# suns_wifi_egse_top_connectors.net
KiCad netlist of a schematic drawn in Altium Designer
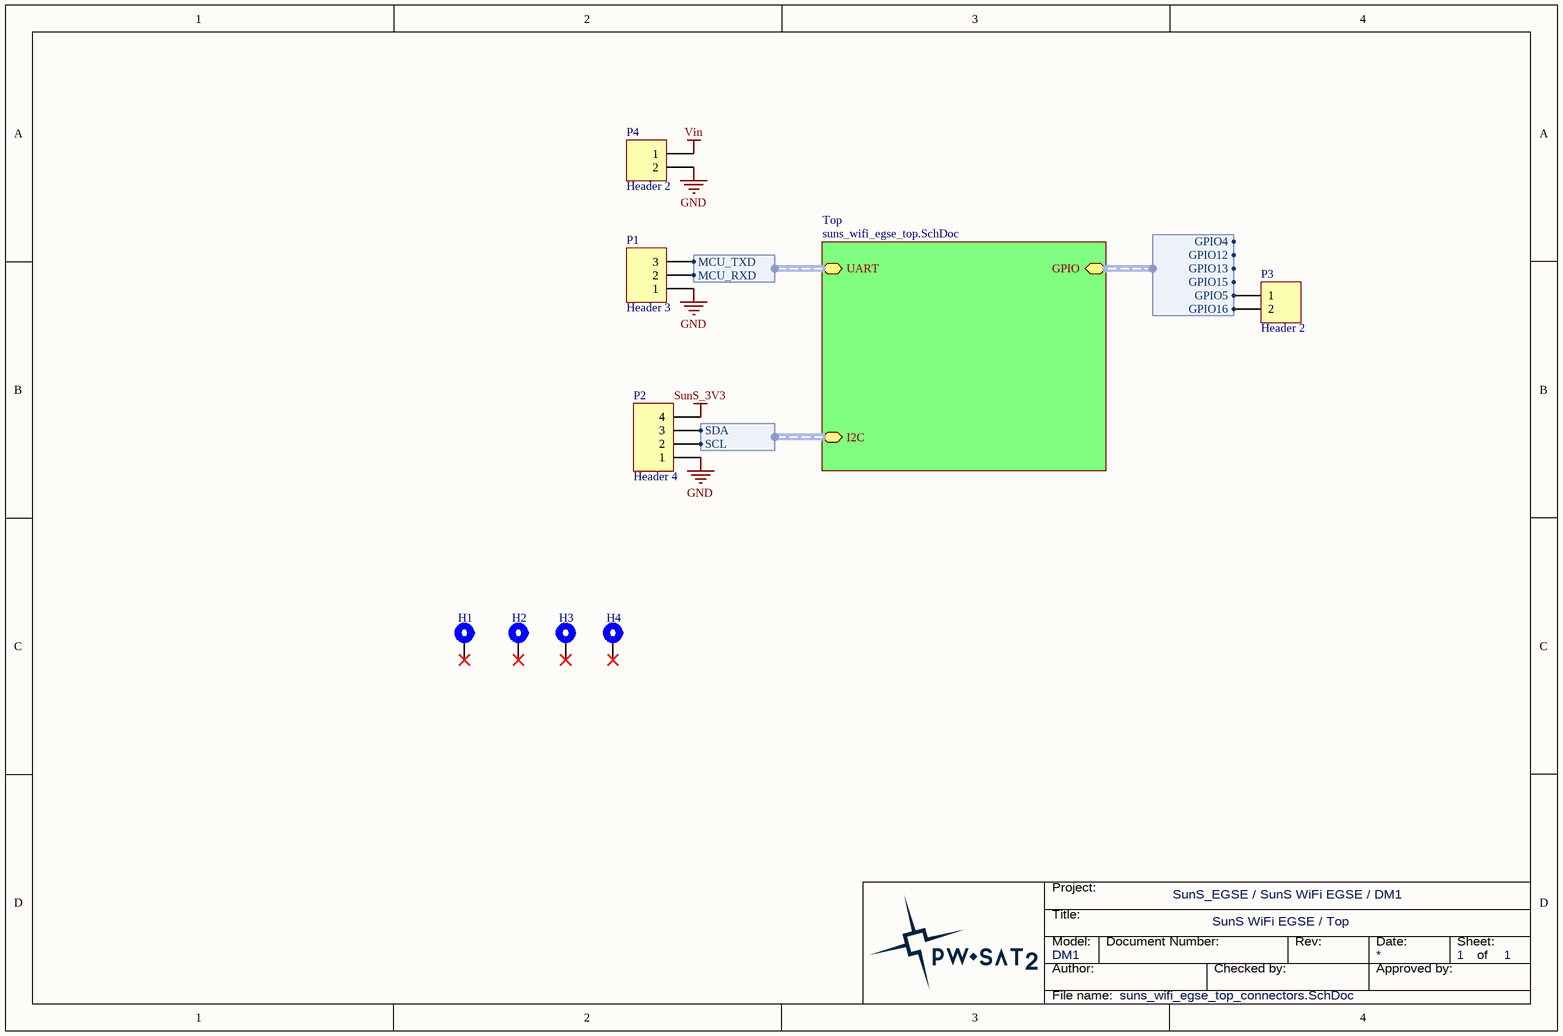
[diagram p0: suns_wifi_egse_top_connectors.SchDoc]

(export (version "E")
  (design (tool "Eeschema 10.0.6"))
  (components
    (comp (ref "H1")
      (value "Mounting Hole")
      (footprint "PC-104_PcbMntHole_M3")
      (description "PCB Mounting Hole")
      (libsource (lib "connectors_printed-circuit-board") (part "MntHole"))
    )
    (comp (ref "H2")
      (value "Mounting Hole")
      (footprint "PC-104_PcbMntHole_M3")
      (description "PCB Mounting Hole")
      (libsource (lib "connectors_printed-circuit-board") (part "MntHole"))
    )
    (comp (ref "H3")
      (value "Mounting Hole")
      (footprint "PC-104_PcbMntHole_M3")
      (description "PCB Mounting Hole")
      (libsource (lib "connectors_printed-circuit-board") (part "MntHole"))
    )
    (comp (ref "H4")
      (value "Mounting Hole")
      (footprint "PC-104_PcbMntHole_M3")
      (description "PCB Mounting Hole")
      (libsource (lib "connectors_printed-circuit-board") (part "MntHole"))
    )
    (comp (ref "P1")
      (value "Header 3")
      (footprint "HEADER1X3H Male")
      (description "Header, 3-Pin")
      (fields (field (name "PUBLISHER") "Altium Limited"))
      (libsource (lib "connectors_printed-circuit-board") (part "Header 3"))
    )
    (comp (ref "P2")
      (value "Header 4")
      (footprint "HEADER 1X4H Male")
      (description "Header, 4-Pin")
      (fields (field (name "PUBLISHER") "Altium Limited"))
      (libsource (lib "connectors_printed-circuit-board") (part "Header 4"))
    )
    (comp (ref "P3")
      (value "Header 2")
      (footprint "HEADER 1X2H Male")
      (description "Header, 2-Pin")
      (fields (field (name "PUBLISHER") "Altium Limited"))
      (libsource (lib "connectors_printed-circuit-board") (part "Header 2"))
    )
    (comp (ref "P4")
      (value "Header 2")
      (footprint "HEADER 1X2H Male")
      (description "Header, 2-Pin")
      (fields (field (name "PUBLISHER") "Altium Limited"))
      (libsource (lib "") (part "Header 2_1"))
    )
  )
  (nets
    (net (code "7") (name "GND") (class "Default")
      (node (ref "P1") (pin "1") (pinfunction "1_1") (pintype "passive"))
      (node (ref "P2") (pin "1") (pinfunction "1_1") (pintype "passive"))
      (node (ref "P4") (pin "2") (pinfunction "2_2") (pintype "passive"))
    )
    (net (code "8") (name "SunS_3V3") (class "Default")
      (node (ref "P2") (pin "4") (pinfunction "4_4") (pintype "passive"))
    )
    (net (code "9") (name "Vin") (class "Default")
      (node (ref "P4") (pin "1") (pinfunction "1_1") (pintype "passive"))
    )
    (net (code "10") (name "unconnected-(H1-Pad1)") (class "Default")
      (node (ref "H1") (pin "1") (pinfunction "1_1") (pintype "passive+no_connect"))
    )
    (net (code "11") (name "unconnected-(H2-Pad1)") (class "Default")
      (node (ref "H2") (pin "1") (pinfunction "1_1") (pintype "passive+no_connect"))
    )
    (net (code "12") (name "unconnected-(H3-Pad1)") (class "Default")
      (node (ref "H3") (pin "1") (pinfunction "1_1") (pintype "passive+no_connect"))
    )
    (net (code "13") (name "unconnected-(H4-Pad1)") (class "Default")
      (node (ref "H4") (pin "1") (pinfunction "1_1") (pintype "passive+no_connect"))
    )
    (net (code "14") (name "unconnected-(P1-Pad2)") (class "Default")
      (node (ref "P1") (pin "2") (pinfunction "2_2") (pintype "passive"))
    )
    (net (code "15") (name "unconnected-(P1-Pad3)") (class "Default")
      (node (ref "P1") (pin "3") (pinfunction "3_3") (pintype "passive"))
    )
    (net (code "16") (name "unconnected-(P2-Pad2)") (class "Default")
      (node (ref "P2") (pin "2") (pinfunction "2_2") (pintype "passive"))
    )
    (net (code "17") (name "unconnected-(P2-Pad3)") (class "Default")
      (node (ref "P2") (pin "3") (pinfunction "3_3") (pintype "passive"))
    )
    (net (code "18") (name "unconnected-(P3-Pad1)") (class "Default")
      (node (ref "P3") (pin "1") (pinfunction "1_1") (pintype "passive"))
    )
    (net (code "19") (name "unconnected-(P3-Pad2)") (class "Default")
      (node (ref "P3") (pin "2") (pinfunction "2_2") (pintype "passive"))
    )
  )
)
